# SparkFun_Dev_ESP32_C3.net
KiCad netlist of a schematic drawn in EAGLE
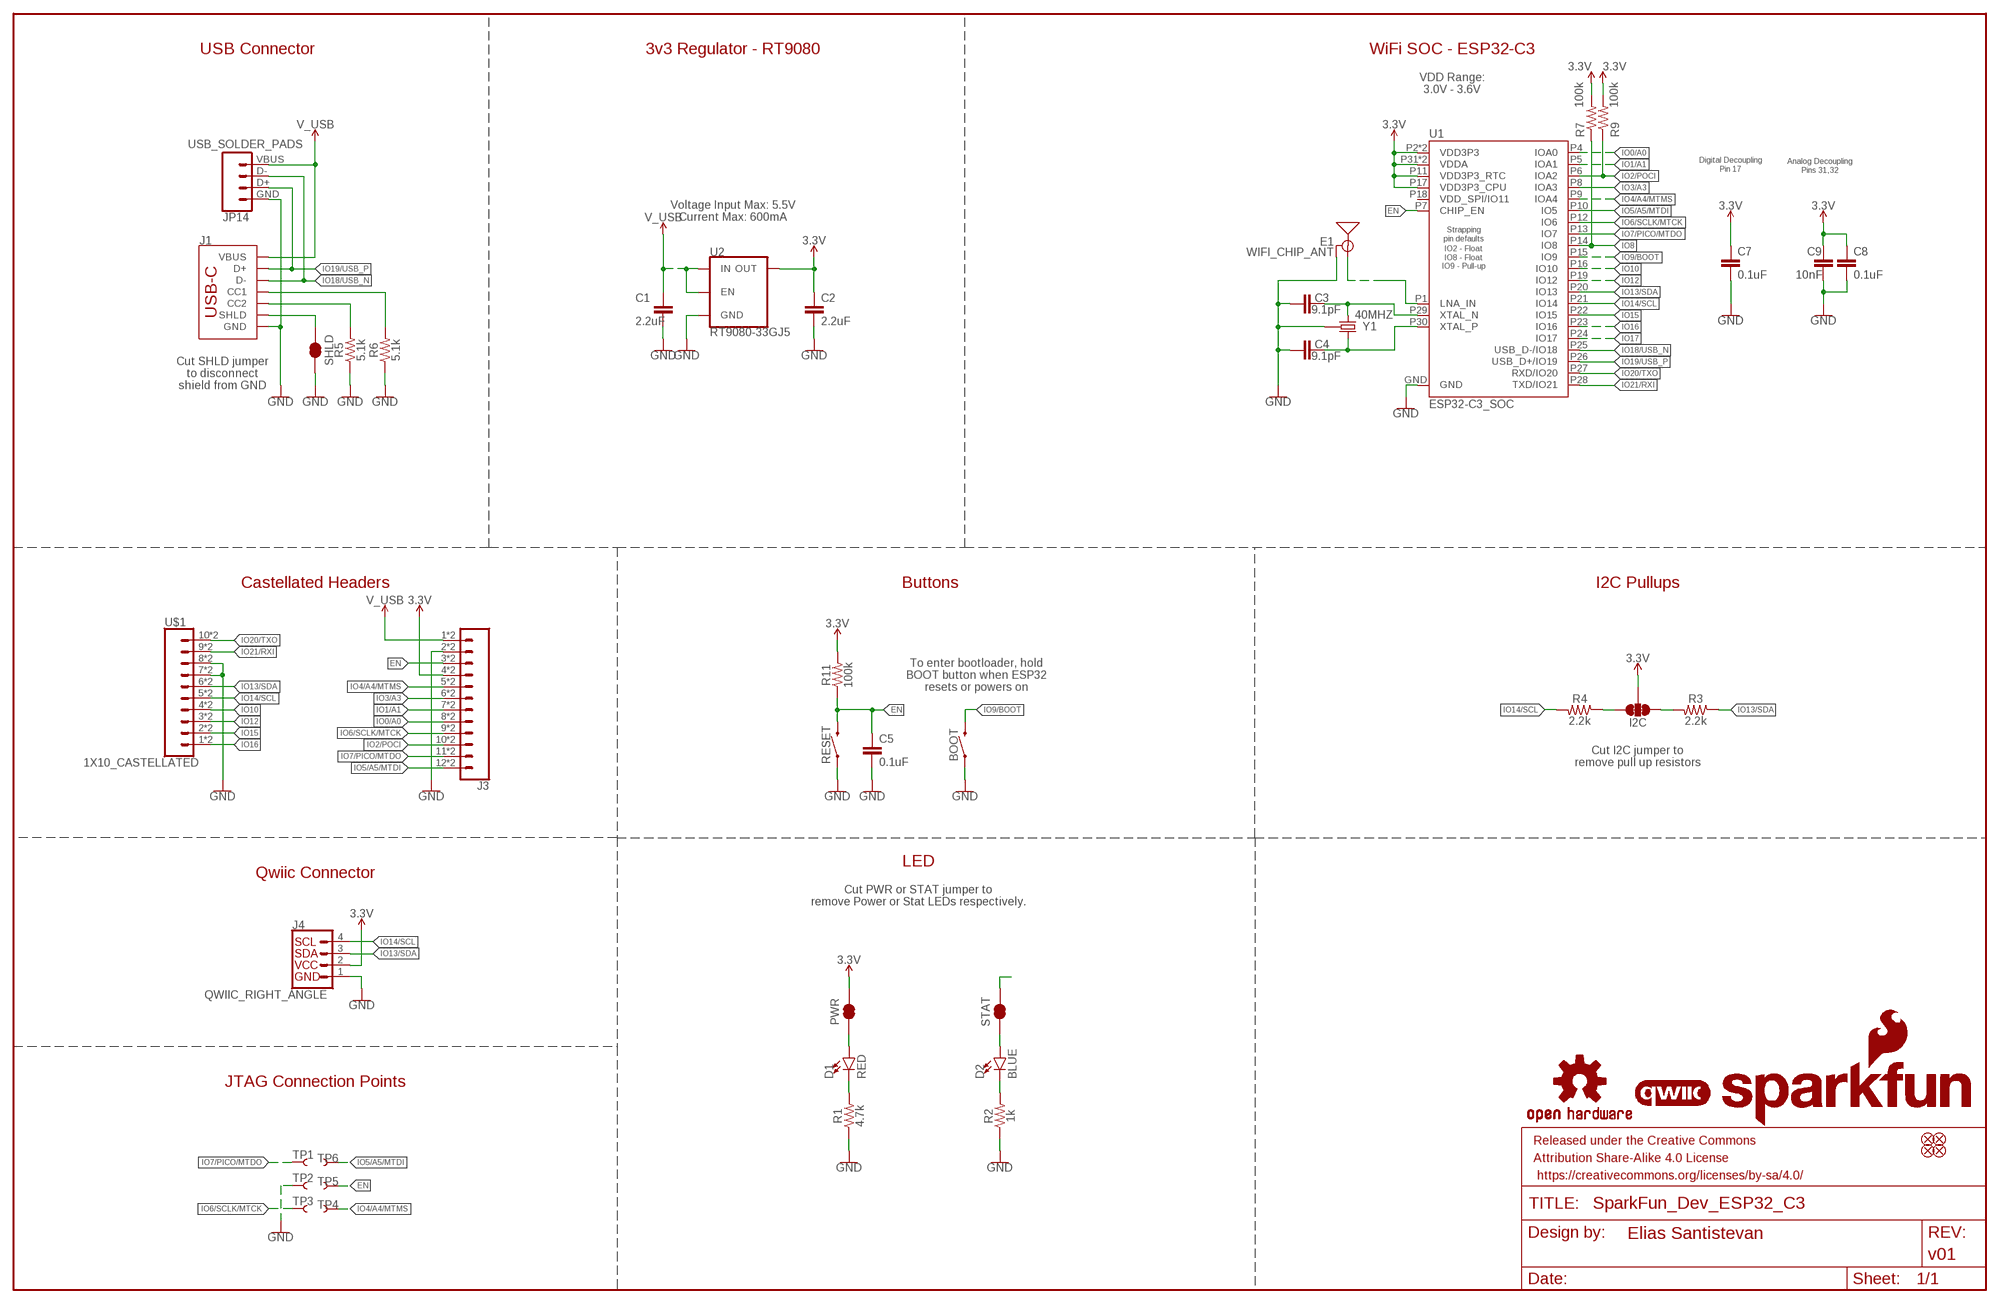
[diagram p0: schematic, sheet 1]

(export (version "E")
  (design (tool "Eeschema 10.0.6"))
  (components
    (comp (ref "BOOT")
      (value "MOMENTARY-SWITCH-SPST-SMD-4.6X2.8MM")
      (footprint "eagle-import:TACTILE_SWITCH_SMD_4.6X2.8MM")
      (libsource (lib "eagle-import") (part "MOMENTARY-SWITCH-SPST-SMD-4.6X2.8MM"))
    )
    (comp (ref "C1")
      (value "2.2uF")
      (footprint "eagle-import:0402-TIGHT")
      (libsource (lib "eagle-import") (part "2.2UF-0402_TIGHT-10V-10%-X5R"))
    )
    (comp (ref "C2")
      (value "2.2uF")
      (footprint "eagle-import:0402-TIGHT")
      (libsource (lib "eagle-import") (part "2.2UF-0402_TIGHT-10V-10%-X5R"))
    )
    (comp (ref "C3")
      (value "9.1pF")
      (footprint "eagle-import:0402-TIGHT")
      (fields (field (name "MOUSER_PART") "609-500R07S9R1CV4T"))
      (libsource (lib "eagle-import") (part "9.1PF-0402-TIGHT"))
    )
    (comp (ref "C4")
      (value "9.1pF")
      (footprint "eagle-import:0402-TIGHT")
      (fields (field (name "MOUSER_PART") "609-500R07S9R1CV4T"))
      (libsource (lib "eagle-import") (part "9.1PF-0402-TIGHT"))
    )
    (comp (ref "C5")
      (value "0.1uF")
      (footprint "eagle-import:0402-TIGHT")
      (libsource (lib "eagle-import") (part "0.1UF-0402T-6.3V-10%-X7R"))
    )
    (comp (ref "C7")
      (value "0.1uF")
      (footprint "eagle-import:0402-TIGHT")
      (libsource (lib "eagle-import") (part "0.1UF-0402T-16V-10%"))
    )
    (comp (ref "C8")
      (value "0.1uF")
      (footprint "eagle-import:0402-TIGHT")
      (libsource (lib "eagle-import") (part "0.1UF-0402T-16V-10%"))
    )
    (comp (ref "C9")
      (value "10nF")
      (footprint "eagle-import:0402-TIGHT")
      (libsource (lib "eagle-import") (part "10NF-0402T-25V-10%"))
    )
    (comp (ref "D1")
      (value "RED")
      (footprint "eagle-import:LED-0603")
      (libsource (lib "eagle-import") (part "LED-RED_0603-KB"))
    )
    (comp (ref "D2")
      (value "BLUE")
      (footprint "eagle-import:LED-0603")
      (libsource (lib "eagle-import") (part "LED-BLUE0603"))
    )
    (comp (ref "E1")
      (value "WIFI_CHIP_ANT")
      (footprint "eagle-import:CHIP_ANT_NO_COURTYARD")
      (libsource (lib "eagle-import") (part "WIFI_CHIP_ANT"))
    )
    (comp (ref "FD1")
      (value "FIDUCIALUFIDUCIAL")
      (footprint "eagle-import:FIDUCIAL-MICRO")
      (libsource (lib "eagle-import") (part "FIDUCIALUFIDUCIAL"))
    )
    (comp (ref "FD2")
      (value "FIDUCIALUFIDUCIAL")
      (footprint "eagle-import:FIDUCIAL-MICRO")
      (libsource (lib "eagle-import") (part "FIDUCIALUFIDUCIAL"))
    )
    (comp (ref "FD3")
      (value "FIDUCIALUFIDUCIAL")
      (footprint "eagle-import:FIDUCIAL-MICRO")
      (libsource (lib "eagle-import") (part "FIDUCIALUFIDUCIAL"))
    )
    (comp (ref "FD4")
      (value "FIDUCIALUFIDUCIAL")
      (footprint "eagle-import:FIDUCIAL-MICRO")
      (libsource (lib "eagle-import") (part "FIDUCIALUFIDUCIAL"))
    )
    (comp (ref "FRAME2")
      (value "FRAME-LEDGER")
      (footprint "eagle-import:CREATIVE_COMMONS")
      (fields (field (name "DESIGNER") "Elias Santistevan") (field (name "REV") "v01"))
      (libsource (lib "eagle-import") (part "FRAME-LEDGER"))
    )
    (comp (ref "I2C")
      (value "JUMPER-SMT_3_2-NC_TRACE_SILK")
      (footprint "eagle-import:SMT-JUMPER_3_2-NC_TRACE_SILK")
      (libsource (lib "eagle-import") (part "JUMPER-SMT_3_2-NC_TRACE_SILK"))
    )
    (comp (ref "J1")
      (value "USB Female Type C Connector")
      (footprint "eagle-import:USB-C-16P_4LAYER-PADS")
      (libsource (lib "eagle-import") (part "USB_C_4-LAYER_PADS"))
    )
    (comp (ref "J3")
      (value "CONN_12CASTELLATED")
      (footprint "eagle-import:1X12_CASTELLATED")
      (libsource (lib "eagle-import") (part "CONN_12CASTELLATED"))
    )
    (comp (ref "J4")
      (value "QWIIC_RIGHT_ANGLE")
      (footprint "eagle-import:JST04_1MM_RA")
      (libsource (lib "eagle-import") (part "QWIIC_CONNECTORJS-1MM"))
    )
    (comp (ref "JP14")
      (value "USB_SOLDER_PADS")
      (footprint "eagle-import:USB-SOLDER-PADS")
      (libsource (lib "eagle-import") (part "USB_SOLDER_PADS"))
    )
    (comp (ref "LOGO1")
      (value "SFE_LOGO_NAME_FLAMEBLANK")
      (footprint "eagle-import:BLANK")
      (libsource (lib "eagle-import") (part "SFE_LOGO_NAME_FLAMEBLANK"))
    )
    (comp (ref "LOGO2")
      (value "QWIIC_LOGO_3MM")
      (footprint "eagle-import:QWIIC_3MM")
      (libsource (lib "eagle-import") (part "QWIIC_LOGO_3MM"))
    )
    (comp (ref "LOGO3")
      (value "OSHW-LOGOS")
      (footprint "eagle-import:OSHW-LOGO-S")
      (libsource (lib "eagle-import") (part "OSHW-LOGOS"))
    )
    (comp (ref "PWR")
      (value "JUMPER-SMT_2_NC_TRACE_SILK")
      (footprint "eagle-import:SMT-JUMPER_2_NC_TRACE_SILK")
      (libsource (lib "eagle-import") (part "JUMPER-SMT_2_NC_TRACE_SILK"))
    )
    (comp (ref "R1")
      (value "4.7k")
      (footprint "eagle-import:0402-TIGHT")
      (libsource (lib "eagle-import") (part "4.7KOHM-0402T-1/16W-1%"))
    )
    (comp (ref "R2")
      (value "1k")
      (footprint "eagle-import:0402-TIGHT")
      (libsource (lib "eagle-import") (part "1KOHM-0402T-1/16W-1%"))
    )
    (comp (ref "R3")
      (value "2.2k")
      (footprint "eagle-import:0402-TIGHT")
      (libsource (lib "eagle-import") (part "2.2KOHM-0402T-1/16W-1%"))
    )
    (comp (ref "R4")
      (value "2.2k")
      (footprint "eagle-import:0402-TIGHT")
      (libsource (lib "eagle-import") (part "2.2KOHM-0402T-1/16W-1%"))
    )
    (comp (ref "R5")
      (value "5.1k")
      (footprint "eagle-import:0402-TIGHT")
      (libsource (lib "eagle-import") (part "5.1KOHM-0402T-1/16W-1%"))
    )
    (comp (ref "R6")
      (value "5.1k")
      (footprint "eagle-import:0402-TIGHT")
      (libsource (lib "eagle-import") (part "5.1KOHM-0402T-1/16W-1%"))
    )
    (comp (ref "R7")
      (value "100k")
      (footprint "eagle-import:0402-TIGHT")
      (libsource (lib "eagle-import") (part "100KOHM-0402T-1/16W-1%"))
    )
    (comp (ref "R9")
      (value "100k")
      (footprint "eagle-import:0402-TIGHT")
      (libsource (lib "eagle-import") (part "100KOHM-0402T-1/16W-1%"))
    )
    (comp (ref "R11")
      (value "100k")
      (footprint "eagle-import:0402-TIGHT")
      (libsource (lib "eagle-import") (part "100KOHM-0402T-1/16W-1%"))
    )
    (comp (ref "RESET")
      (value "MOMENTARY-SWITCH-SPST-SMD-4.6X2.8MM")
      (footprint "eagle-import:TACTILE_SWITCH_SMD_4.6X2.8MM")
      (libsource (lib "eagle-import") (part "MOMENTARY-SWITCH-SPST-SMD-4.6X2.8MM"))
    )
    (comp (ref "SHLD")
      (value "JUMPER-SMT_2_NC_TRACE_SILK")
      (footprint "eagle-import:SMT-JUMPER_2_NC_TRACE_SILK")
      (libsource (lib "eagle-import") (part "JUMPER-SMT_2_NC_TRACE_SILK"))
    )
    (comp (ref "STAT")
      (value "JUMPER-SMT_2_NC_TRACE_SILK")
      (footprint "eagle-import:SMT-JUMPER_2_NC_TRACE_SILK")
      (libsource (lib "eagle-import") (part "JUMPER-SMT_2_NC_TRACE_SILK"))
    )
    (comp (ref "TP1")
      (value "TEST-POINT3X5")
      (footprint "eagle-import:PAD.03X.05")
      (libsource (lib "eagle-import") (part "TEST-POINT3X5"))
    )
    (comp (ref "TP2")
      (value "TEST-POINT3X5")
      (footprint "eagle-import:PAD.03X.05")
      (libsource (lib "eagle-import") (part "TEST-POINT3X5"))
    )
    (comp (ref "TP3")
      (value "TEST-POINT3X5")
      (footprint "eagle-import:PAD.03X.05")
      (libsource (lib "eagle-import") (part "TEST-POINT3X5"))
    )
    (comp (ref "TP4")
      (value "TEST-POINT3X5")
      (footprint "eagle-import:PAD.03X.05")
      (libsource (lib "eagle-import") (part "TEST-POINT3X5"))
    )
    (comp (ref "TP5")
      (value "TEST-POINT3X5")
      (footprint "eagle-import:PAD.03X.05")
      (libsource (lib "eagle-import") (part "TEST-POINT3X5"))
    )
    (comp (ref "TP6")
      (value "TEST-POINT3X5")
      (footprint "eagle-import:PAD.03X.05")
      (libsource (lib "eagle-import") (part "TEST-POINT3X5"))
    )
    (comp (ref "U$1")
      (value "1X10_CASTELLATED")
      (footprint "eagle-import:1X10_CASTELLATED")
      (libsource (lib "eagle-import") (part "1X10_CASTELLATED"))
    )
    (comp (ref "U1")
      (value "ESP32-C3_SOC")
      (footprint "eagle-import:QFN32")
      (libsource (lib "eagle-import") (part "ESP32-C3_SOC"))
    )
    (comp (ref "U2")
      (value "RT9080-33GJ5")
      (footprint "eagle-import:SOT23-5")
      (libsource (lib "eagle-import") (part "V_REG_RT9080"))
    )
    (comp (ref "Y1")
      (value "40MHZ")
      (footprint "eagle-import:CRYSTAL-SMD-2X2.5MM")
      (libsource (lib "eagle-import") (part "CRYSTAL-40MHZ-SMD-2X2.5MM"))
    )
  )
  (nets
    (net (code "1") (name "3.3V") (class "Default")
      (node (ref "C2") (pin "1") (pinfunction "1_1") (pintype "passive"))
      (node (ref "C7") (pin "1") (pinfunction "1_1") (pintype "passive"))
      (node (ref "C8") (pin "1") (pinfunction "1_1") (pintype "passive"))
      (node (ref "C9") (pin "1") (pinfunction "1_1") (pintype "passive"))
      (node (ref "I2C") (pin "2") (pinfunction "2_2") (pintype "passive"))
      (node (ref "J3") (pin "4") (pinfunction "4_4") (pintype "passive"))
      (node (ref "J3") (pin "4B") (pinfunction "4_4B") (pintype "passive"))
      (node (ref "J4") (pin "2") (pinfunction "2_2") (pintype "power_in"))
      (node (ref "PWR") (pin "2") (pinfunction "2_2") (pintype "passive"))
      (node (ref "R11") (pin "2") (pinfunction "2_2") (pintype "passive"))
      (node (ref "R7") (pin "2") (pinfunction "2_2") (pintype "passive"))
      (node (ref "R9") (pin "2") (pinfunction "2_2") (pintype "passive"))
      (node (ref "U1") (pin "P11") (pinfunction "VDD3P3_RTC_P11") (pintype "bidirectional"))
      (node (ref "U1") (pin "P17") (pinfunction "VDD3P3_CPU_P17") (pintype "bidirectional"))
      (node (ref "U1") (pin "P2") (pinfunction "VDD3P3_P2") (pintype "bidirectional"))
      (node (ref "U1") (pin "P3") (pinfunction "VDD3P3_P3") (pintype "bidirectional"))
      (node (ref "U1") (pin "P31") (pinfunction "VDDA_P31") (pintype "bidirectional"))
      (node (ref "U1") (pin "P32") (pinfunction "VDDA_P32") (pintype "bidirectional"))
      (node (ref "U2") (pin "5") (pinfunction "OUT_5") (pintype "passive"))
    )
    (net (code "2") (name "EN") (class "Default")
      (node (ref "C5") (pin "1") (pinfunction "1_1") (pintype "passive"))
      (node (ref "J3") (pin "3") (pinfunction "3_3") (pintype "passive"))
      (node (ref "J3") (pin "3B") (pinfunction "3_3B") (pintype "passive"))
      (node (ref "R11") (pin "1") (pinfunction "1_1") (pintype "passive"))
      (node (ref "RESET") (pin "3") (pinfunction "2_3") (pintype "passive"))
      (node (ref "RESET") (pin "4") (pinfunction "2_4") (pintype "passive"))
      (node (ref "TP5") (pin "1") (pinfunction "1_1") (pintype "bidirectional"))
      (node (ref "U1") (pin "P7") (pinfunction "CHIP_EN_P7") (pintype "bidirectional"))
    )
    (net (code "3") (name "GND") (class "Default")
      (node (ref "BOOT") (pin "1") (pinfunction "1_1") (pintype "passive"))
      (node (ref "BOOT") (pin "2") (pinfunction "1_2") (pintype "passive"))
      (node (ref "C1") (pin "2") (pinfunction "2_2") (pintype "passive"))
      (node (ref "C2") (pin "2") (pinfunction "2_2") (pintype "passive"))
      (node (ref "C3") (pin "1") (pinfunction "1_1") (pintype "passive"))
      (node (ref "C4") (pin "1") (pinfunction "1_1") (pintype "passive"))
      (node (ref "C5") (pin "2") (pinfunction "2_2") (pintype "passive"))
      (node (ref "C7") (pin "2") (pinfunction "2_2") (pintype "passive"))
      (node (ref "C8") (pin "2") (pinfunction "2_2") (pintype "passive"))
      (node (ref "C9") (pin "2") (pinfunction "2_2") (pintype "passive"))
      (node (ref "E1") (pin "P3") (pinfunction "GND_P3") (pintype "bidirectional"))
      (node (ref "E1") (pin "P4") (pinfunction "GND_P4") (pintype "bidirectional"))
      (node (ref "J1") (pin "GND") (pinfunction "GND_GND") (pintype "bidirectional"))
      (node (ref "J1") (pin "GND2") (pinfunction "GND_GND2") (pintype "bidirectional"))
      (node (ref "J3") (pin "2") (pinfunction "2_2") (pintype "passive"))
      (node (ref "J3") (pin "2B") (pinfunction "2_2B") (pintype "passive"))
      (node (ref "J4") (pin "1") (pinfunction "1_1") (pintype "power_in"))
      (node (ref "JP14") (pin "GND") (pinfunction "4_GND") (pintype "passive"))
      (node (ref "R1") (pin "1") (pinfunction "1_1") (pintype "passive"))
      (node (ref "R2") (pin "1") (pinfunction "1_1") (pintype "passive"))
      (node (ref "R5") (pin "1") (pinfunction "1_1") (pintype "passive"))
      (node (ref "R6") (pin "1") (pinfunction "1_1") (pintype "passive"))
      (node (ref "RESET") (pin "1") (pinfunction "1_1") (pintype "passive"))
      (node (ref "RESET") (pin "2") (pinfunction "1_2") (pintype "passive"))
      (node (ref "SHLD") (pin "2") (pinfunction "2_2") (pintype "passive"))
      (node (ref "TP2") (pin "1") (pinfunction "1_1") (pintype "bidirectional"))
      (node (ref "U$1") (pin "7") (pinfunction "7_7") (pintype "passive"))
      (node (ref "U$1") (pin "7B") (pinfunction "7_7B") (pintype "passive"))
      (node (ref "U$1") (pin "8") (pinfunction "8_8") (pintype "passive"))
      (node (ref "U$1") (pin "8B") (pinfunction "8_8B") (pintype "passive"))
      (node (ref "U1") (pin "GND") (pinfunction "GND_GND") (pintype "bidirectional"))
      (node (ref "U2") (pin "2") (pinfunction "GND_2") (pintype "input"))
      (node (ref "Y1") (pin "P2") (pinfunction "GND_P2") (pintype "power_in"))
      (node (ref "Y1") (pin "P4") (pinfunction "GND_P4") (pintype "power_in"))
    )
    (net (code "4") (name "IO0{slash}A0") (class "Default")
      (node (ref "J3") (pin "8") (pinfunction "8_8") (pintype "passive"))
      (node (ref "J3") (pin "8B") (pinfunction "8_8B") (pintype "passive"))
      (node (ref "U1") (pin "P4") (pinfunction "IOA0_P4") (pintype "bidirectional"))
    )
    (net (code "5") (name "IO1{slash}A1") (class "Default")
      (node (ref "J3") (pin "7") (pinfunction "7_7") (pintype "passive"))
      (node (ref "J3") (pin "7B") (pinfunction "7_7B") (pintype "passive"))
      (node (ref "U1") (pin "P5") (pinfunction "IOA1_P5") (pintype "bidirectional"))
    )
    (net (code "6") (name "IO2{slash}POCI") (class "Default")
      (node (ref "J3") (pin "10") (pinfunction "10_10") (pintype "passive"))
      (node (ref "J3") (pin "10B") (pinfunction "10_10B") (pintype "passive"))
      (node (ref "R9") (pin "1") (pinfunction "1_1") (pintype "passive"))
      (node (ref "U1") (pin "P6") (pinfunction "IOA2_P6") (pintype "bidirectional"))
    )
    (net (code "7") (name "IO3{slash}A3") (class "Default")
      (node (ref "J3") (pin "6") (pinfunction "6_6") (pintype "passive"))
      (node (ref "J3") (pin "6B") (pinfunction "6_6B") (pintype "passive"))
      (node (ref "U1") (pin "P8") (pinfunction "IOA3_P8") (pintype "bidirectional"))
    )
    (net (code "8") (name "IO4{slash}A4{slash}MTMS") (class "Default")
      (node (ref "J3") (pin "5") (pinfunction "5_5") (pintype "passive"))
      (node (ref "J3") (pin "5B") (pinfunction "5_5B") (pintype "passive"))
      (node (ref "TP4") (pin "1") (pinfunction "1_1") (pintype "bidirectional"))
      (node (ref "U1") (pin "P9") (pinfunction "IOA4_P9") (pintype "bidirectional"))
    )
    (net (code "9") (name "IO5{slash}A5{slash}MTDI") (class "Default")
      (node (ref "J3") (pin "12") (pinfunction "12_12") (pintype "passive"))
      (node (ref "J3") (pin "12B") (pinfunction "12_12B") (pintype "passive"))
      (node (ref "TP6") (pin "1") (pinfunction "1_1") (pintype "bidirectional"))
      (node (ref "U1") (pin "P10") (pinfunction "IO5_P10") (pintype "bidirectional"))
    )
    (net (code "10") (name "IO6{slash}SCLK{slash}MTCK") (class "Default")
      (node (ref "J3") (pin "9") (pinfunction "9_9") (pintype "passive"))
      (node (ref "J3") (pin "9B") (pinfunction "9_9B") (pintype "passive"))
      (node (ref "TP3") (pin "1") (pinfunction "1_1") (pintype "bidirectional"))
      (node (ref "U1") (pin "P12") (pinfunction "IO6_P12") (pintype "bidirectional"))
    )
    (net (code "11") (name "IO7{slash}PICO{slash}MTDO") (class "Default")
      (node (ref "J3") (pin "11") (pinfunction "11_11") (pintype "passive"))
      (node (ref "J3") (pin "11B") (pinfunction "11_11B") (pintype "passive"))
      (node (ref "TP1") (pin "1") (pinfunction "1_1") (pintype "bidirectional"))
      (node (ref "U1") (pin "P13") (pinfunction "IO7_P13") (pintype "bidirectional"))
    )
    (net (code "12") (name "IO8") (class "Default")
      (node (ref "R7") (pin "1") (pinfunction "1_1") (pintype "passive"))
      (node (ref "U1") (pin "P14") (pinfunction "IO8_P14") (pintype "bidirectional"))
    )
    (net (code "13") (name "IO9{slash}BOOT") (class "Default")
      (node (ref "BOOT") (pin "3") (pinfunction "2_3") (pintype "passive"))
      (node (ref "BOOT") (pin "4") (pinfunction "2_4") (pintype "passive"))
      (node (ref "U1") (pin "P15") (pinfunction "IO9_P15") (pintype "bidirectional"))
    )
    (net (code "14") (name "IO10") (class "Default")
      (node (ref "U$1") (pin "4") (pinfunction "4_4") (pintype "passive"))
      (node (ref "U$1") (pin "4B") (pinfunction "4_4B") (pintype "passive"))
      (node (ref "U1") (pin "P16") (pinfunction "IO10_P16") (pintype "bidirectional"))
    )
    (net (code "15") (name "IO12") (class "Default")
      (node (ref "U$1") (pin "3") (pinfunction "3_3") (pintype "passive"))
      (node (ref "U$1") (pin "3B") (pinfunction "3_3B") (pintype "passive"))
      (node (ref "U1") (pin "P19") (pinfunction "IO12_P19") (pintype "bidirectional"))
    )
    (net (code "16") (name "IO13{slash}SDA") (class "Default")
      (node (ref "J4") (pin "3") (pinfunction "3_3") (pintype "passive"))
      (node (ref "R3") (pin "1") (pinfunction "1_1") (pintype "passive"))
      (node (ref "U$1") (pin "6") (pinfunction "6_6") (pintype "passive"))
      (node (ref "U$1") (pin "6B") (pinfunction "6_6B") (pintype "passive"))
      (node (ref "U1") (pin "P20") (pinfunction "IO13_P20") (pintype "bidirectional"))
    )
    (net (code "17") (name "IO14{slash}SCL") (class "Default")
      (node (ref "J4") (pin "4") (pinfunction "4_4") (pintype "passive"))
      (node (ref "R4") (pin "2") (pinfunction "2_2") (pintype "passive"))
      (node (ref "U$1") (pin "5") (pinfunction "5_5") (pintype "passive"))
      (node (ref "U$1") (pin "5B") (pinfunction "5_5B") (pintype "passive"))
      (node (ref "U1") (pin "P21") (pinfunction "IO14_P21") (pintype "bidirectional"))
    )
    (net (code "18") (name "IO15") (class "Default")
      (node (ref "U$1") (pin "2") (pinfunction "2_2") (pintype "passive"))
      (node (ref "U$1") (pin "2B") (pinfunction "2_2B") (pintype "passive"))
      (node (ref "U1") (pin "P22") (pinfunction "IO15_P22") (pintype "bidirectional"))
    )
    (net (code "19") (name "IO16") (class "Default")
      (node (ref "U$1") (pin "1") (pinfunction "1_1") (pintype "passive"))
      (node (ref "U$1") (pin "1B") (pinfunction "1_1B") (pintype "passive"))
      (node (ref "U1") (pin "P23") (pinfunction "IO16_P23") (pintype "bidirectional"))
    )
    (net (code "20") (name "IO17") (class "Default")
      (node (ref "U1") (pin "P24") (pinfunction "IO17_P24") (pintype "bidirectional"))
    )
    (net (code "21") (name "IO18{slash}USB_N") (class "Default")
      (node (ref "J1") (pin "A7") (pinfunction "D-_A7") (pintype "bidirectional"))
      (node (ref "J1") (pin "B7") (pinfunction "D-_B7") (pintype "bidirectional"))
      (node (ref "JP14") (pin "D-") (pinfunction "2_D-") (pintype "passive"))
      (node (ref "U1") (pin "P25") (pinfunction "USB_D-/IO18_P25") (pintype "bidirectional"))
    )
    (net (code "22") (name "IO19{slash}USB_P") (class "Default")
      (node (ref "J1") (pin "A6") (pinfunction "D+_A6") (pintype "bidirectional"))
      (node (ref "J1") (pin "B6") (pinfunction "D+_B6") (pintype "bidirectional"))
      (node (ref "JP14") (pin "D+") (pinfunction "3_D+") (pintype "passive"))
      (node (ref "U1") (pin "P26") (pinfunction "USB_D+/IO19_P26") (pintype "bidirectional"))
    )
    (net (code "23") (name "IO20{slash}TXO") (class "Default")
      (node (ref "U$1") (pin "10") (pinfunction "10_10") (pintype "passive"))
      (node (ref "U$1") (pin "10B") (pinfunction "10_10B") (pintype "passive"))
      (node (ref "U1") (pin "P27") (pinfunction "RXD/IO20_P27") (pintype "bidirectional"))
    )
    (net (code "24") (name "IO21{slash}RXI") (class "Default")
      (node (ref "U$1") (pin "9") (pinfunction "9_9") (pintype "passive"))
      (node (ref "U$1") (pin "9B") (pinfunction "9_9B") (pintype "passive"))
      (node (ref "U1") (pin "P28") (pinfunction "TXD/IO21_P28") (pintype "bidirectional"))
    )
    (net (code "25") (name "Net-(D1-PadA)") (class "Default")
      (node (ref "D1") (pin "A") (pinfunction "A_A") (pintype "passive"))
      (node (ref "PWR") (pin "1") (pinfunction "1_1") (pintype "passive"))
    )
    (net (code "26") (name "Net-(D1-PadC)") (class "Default")
      (node (ref "D1") (pin "C") (pinfunction "C_C") (pintype "passive"))
      (node (ref "R1") (pin "2") (pinfunction "2_2") (pintype "passive"))
    )
    (net (code "27") (name "Net-(D2-PadA)") (class "Default")
      (node (ref "D2") (pin "A") (pinfunction "A_A") (pintype "passive"))
      (node (ref "STAT") (pin "1") (pinfunction "1_1") (pintype "passive"))
    )
    (net (code "28") (name "Net-(D2-PadC)") (class "Default")
      (node (ref "D2") (pin "C") (pinfunction "C_C") (pintype "passive"))
      (node (ref "R2") (pin "2") (pinfunction "2_2") (pintype "passive"))
    )
    (net (code "29") (name "Net-(E1-SIGNAL)") (class "Default")
      (node (ref "E1") (pin "P1") (pinfunction "SIGNAL_P1") (pintype "bidirectional"))
      (node (ref "U1") (pin "P1") (pinfunction "LNA_IN_P1") (pintype "bidirectional"))
    )
    (net (code "30") (name "Net-(I2C-Pad1)") (class "Default")
      (node (ref "I2C") (pin "1") (pinfunction "1_1") (pintype "passive"))
      (node (ref "R4") (pin "1") (pinfunction "1_1") (pintype "passive"))
    )
    (net (code "31") (name "Net-(I2C-Pad3)") (class "Default")
      (node (ref "I2C") (pin "3") (pinfunction "3_3") (pintype "passive"))
      (node (ref "R3") (pin "2") (pinfunction "2_2") (pintype "passive"))
    )
    (net (code "32") (name "Net-(J1-CC1)") (class "Default")
      (node (ref "J1") (pin "A5") (pinfunction "CC1_A5") (pintype "bidirectional"))
      (node (ref "R6") (pin "2") (pinfunction "2_2") (pintype "passive"))
    )
    (net (code "33") (name "Net-(J1-CC2)") (class "Default")
      (node (ref "J1") (pin "B5") (pinfunction "CC2_B5") (pintype "bidirectional"))
      (node (ref "R5") (pin "2") (pinfunction "2_2") (pintype "passive"))
    )
    (net (code "34") (name "Net-(J1-SHLD-PadSHLD1)") (class "Default")
      (node (ref "J1") (pin "SHLD1") (pinfunction "SHLD_SHLD1") (pintype "bidirectional"))
      (node (ref "J1") (pin "SHLD2") (pinfunction "SHLD_SHLD2") (pintype "bidirectional"))
      (node (ref "J1") (pin "SHLD3") (pinfunction "SHLD_SHLD3") (pintype "bidirectional"))
      (node (ref "J1") (pin "SHLD4") (pinfunction "SHLD_SHLD4") (pintype "bidirectional"))
      (node (ref "SHLD") (pin "1") (pinfunction "1_1") (pintype "passive"))
    )
    (net (code "35") (name "Net-(U1-XTAL_N)") (class "Default")
      (node (ref "C3") (pin "2") (pinfunction "2_2") (pintype "passive"))
      (node (ref "U1") (pin "P29") (pinfunction "XTAL_N_P29") (pintype "bidirectional"))
      (node (ref "Y1") (pin "P1") (pinfunction "1_P1") (pintype "passive"))
    )
    (net (code "36") (name "Net-(U1-XTAL_P)") (class "Default")
      (node (ref "C4") (pin "2") (pinfunction "2_2") (pintype "passive"))
      (node (ref "U1") (pin "P30") (pinfunction "XTAL_P_P30") (pintype "bidirectional"))
      (node (ref "Y1") (pin "P3") (pinfunction "2_P3") (pintype "passive"))
    )
    (net (code "37") (name "V_USB") (class "Default")
      (node (ref "C1") (pin "1") (pinfunction "1_1") (pintype "passive"))
      (node (ref "J1") (pin "VBUS1") (pinfunction "VBUS_VBUS1") (pintype "bidirectional"))
      (node (ref "J1") (pin "VBUS2") (pinfunction "VBUS_VBUS2") (pintype "bidirectional"))
      (node (ref "J3") (pin "1") (pinfunction "1_1") (pintype "passive"))
      (node (ref "J3") (pin "1B") (pinfunction "1_1B") (pintype "passive"))
      (node (ref "JP14") (pin "VBUS") (pinfunction "1_VBUS") (pintype "passive"))
      (node (ref "U2") (pin "1") (pinfunction "IN_1") (pintype "input"))
      (node (ref "U2") (pin "3") (pinfunction "EN_3") (pintype "input"))
    )
    (net (code "38") (name "unconnected-(STAT-Pad2)") (class "Default")
      (node (ref "STAT") (pin "2") (pinfunction "2_2") (pintype "passive"))
    )
    (net (code "39") (name "unconnected-(U1-VDD_SPI{slash}IO11-PadP18)") (class "Default")
      (node (ref "U1") (pin "P18") (pinfunction "VDD_SPI/IO11_P18") (pintype "bidirectional"))
    )
  )
)
